# legdrive.net
KiCad netlist of a schematic drawn in Altium Designer
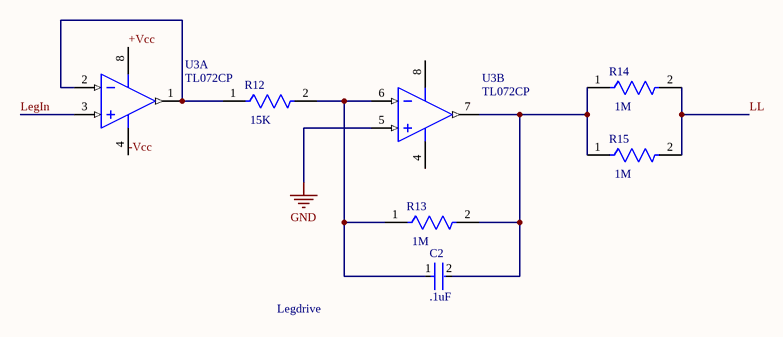
[diagram p0: legdrive.SchDoc]

(export (version "E")
  (design (tool "Eeschema 10.0.6"))
  (components
    (comp (ref "C2")
      (value ".1uF")
      (footprint "FP-K15H5-MFG")
      (description "CAP CER 0.1UF 50V X7R RADIAL")
      (fields (field (name "VOLTAGE") "50V") (field (name "TOLERANCE") "10%"))
      (libsource (lib "Altium Content Vault") (part "11868f565c42a9108669ba33697ecf6"))
    )
    (comp (ref "R12")
      (value "15K")
      (footprint "FP-CFR-25-MFG")
      (description "RES 10 OHM 1/4W 5% AXIAL")
      (fields (field (name "TOLERANCE") "5%"))
      (libsource (lib "Altium Content Vault") (part "1029c3af85768c4190bb7ad29bc67b5"))
    )
    (comp (ref "R13")
      (value "1M")
      (footprint "FP-CFR-25-MFG")
      (description "RES 10 OHM 1/4W 5% AXIAL")
      (fields (field (name "TOLERANCE") "5%"))
      (libsource (lib "Altium Content Vault") (part "1029c3af85768c4190bb7ad29bc67b5"))
    )
    (comp (ref "R14")
      (value "1M")
      (footprint "FP-CFR-25-MFG")
      (description "RES 10 OHM 1/4W 5% AXIAL")
      (fields (field (name "TOLERANCE") "5%"))
      (libsource (lib "Altium Content Vault") (part "1029c3af85768c4190bb7ad29bc67b5"))
    )
    (comp (ref "R15")
      (value "1M")
      (footprint "FP-CFR-25-MFG")
      (description "RES 10 OHM 1/4W 5% AXIAL")
      (fields (field (name "TOLERANCE") "5%"))
      (libsource (lib "Altium Content Vault") (part "1029c3af85768c4190bb7ad29bc67b5"))
    )
    (comp (ref "U3")
      (value "TL072CP")
      (footprint "P0008A")
      (fields (field (name "MANUFACTURER") "Texas Instruments"))
      (libsource (lib "Altium Content Vault") (part "TI-AMP-D6-2-8_D"))
    )
  )
  (nets
    (net (code "1") (name "/+Vcc") (class "Default")
      (node (ref "U3") (pin "8") (pinfunction "VCC+_8") (pintype "power_in"))
    )
    (net (code "2") (name "/-Vcc") (class "Default")
      (node (ref "U3") (pin "4") (pinfunction "VCC-_4") (pintype "power_in"))
    )
    (net (code "3") (name "/LL") (class "Default")
      (node (ref "R14") (pin "2") (pinfunction "2_2") (pintype "passive"))
      (node (ref "R15") (pin "2") (pinfunction "2_2") (pintype "passive"))
    )
    (net (code "4") (name "/LegIn") (class "Default")
      (node (ref "U3") (pin "3") (pinfunction "IN1+_3") (pintype "input"))
    )
    (net (code "5") (name "GND") (class "Default")
      (node (ref "U3") (pin "5") (pinfunction "IN2+_5") (pintype "input"))
    )
    (net (code "6") (name "Net-(U3A-IN1-)") (class "Default")
      (node (ref "R12") (pin "1") (pinfunction "1_1") (pintype "passive"))
      (node (ref "U3") (pin "1") (pinfunction "OUT1_1") (pintype "output"))
      (node (ref "U3") (pin "2") (pinfunction "IN1-_2") (pintype "input"))
    )
    (net (code "7") (name "Net-(U3B-IN2-)") (class "Default")
      (node (ref "C2") (pin "1") (pinfunction "1_1") (pintype "passive"))
      (node (ref "R12") (pin "2") (pinfunction "2_2") (pintype "passive"))
      (node (ref "R13") (pin "1") (pinfunction "1_1") (pintype "passive"))
      (node (ref "U3") (pin "6") (pinfunction "IN2-_6") (pintype "input"))
    )
    (net (code "8") (name "Net-(U3B-OUT2)") (class "Default")
      (node (ref "C2") (pin "2") (pinfunction "2_2") (pintype "passive"))
      (node (ref "R13") (pin "2") (pinfunction "2_2") (pintype "passive"))
      (node (ref "R14") (pin "1") (pinfunction "1_1") (pintype "passive"))
      (node (ref "R15") (pin "1") (pinfunction "1_1") (pintype "passive"))
      (node (ref "U3") (pin "7") (pinfunction "OUT2_7") (pintype "output"))
    )
    (net (code "9") (name "unconnected-(U3B-VCC+-Pad8)") (class "Default")
      (node (ref "U3") (pin "8") (pinfunction "VCC+_8") (pintype "power_in"))
    )
    (net (code "10") (name "unconnected-(U3B-VCC--Pad4)") (class "Default")
      (node (ref "U3") (pin "4") (pinfunction "VCC-_4") (pintype "power_in"))
    )
  )
)
